# Sheet1_Drone.net
KiCad netlist of a schematic drawn in Altium Designer
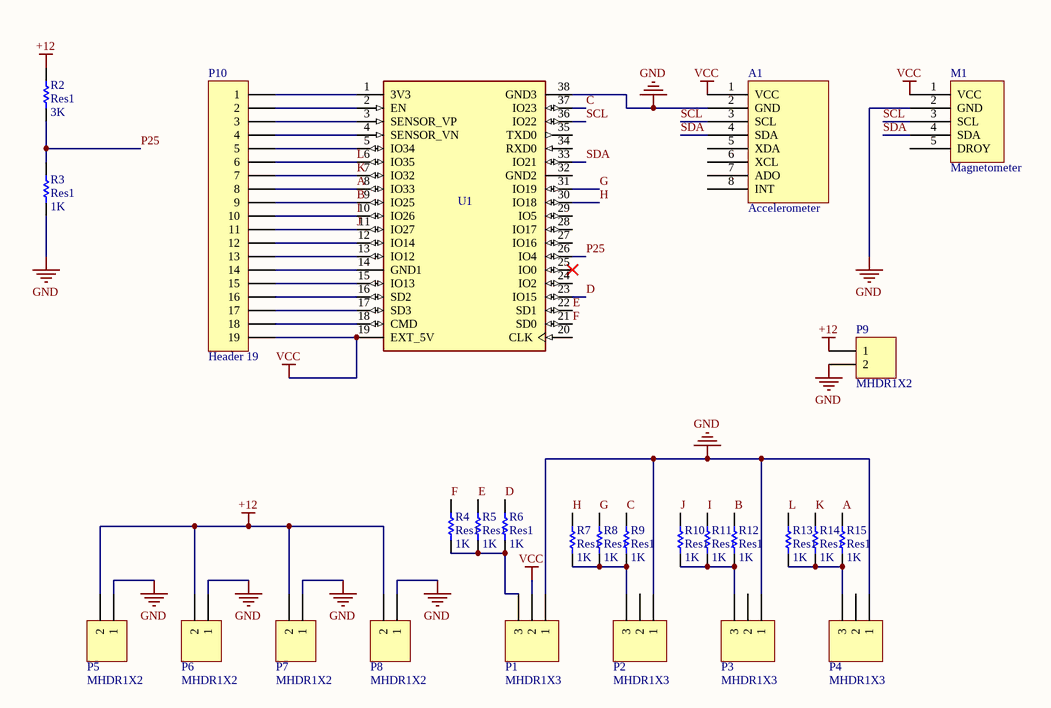
[diagram p0: Sheet1_Drone.SchDoc]

(export (version "E")
  (design (tool "Eeschema 10.0.6"))
  (components
    (comp (ref "A1")
      (value "Accelerometer")
      (footprint "Accelerometer")
      (libsource (lib "Schlib1_Drone") (part "HW123_Accelerator"))
    )
    (comp (ref "M1")
      (value "Magnetometer")
      (footprint "Magnetometer")
      (libsource (lib "Schlib1_Drone") (part "Magnetometer"))
    )
    (comp (ref "P1")
      (value "MHDR1X3")
      (footprint "SAMTEC_BBS-102-X-X")
      (description "Header, 3-Pin")
      (fields (field (name "PUBLISHER") "Altium Limited"))
      (libsource (lib "Miscellaneous Connectors") (part "MHDR1X3"))
    )
    (comp (ref "P2")
      (value "MHDR1X3")
      (footprint "SAMTEC_BBS-102-X-X")
      (description "Header, 3-Pin")
      (fields (field (name "PUBLISHER") "Altium Limited"))
      (libsource (lib "Miscellaneous Connectors") (part "MHDR1X3"))
    )
    (comp (ref "P3")
      (value "MHDR1X3")
      (footprint "SAMTEC_BBS-102-X-X")
      (description "Header, 3-Pin")
      (fields (field (name "PUBLISHER") "Altium Limited"))
      (libsource (lib "Miscellaneous Connectors") (part "MHDR1X3"))
    )
    (comp (ref "P4")
      (value "MHDR1X3")
      (footprint "SAMTEC_BBS-102-X-X")
      (description "Header, 3-Pin")
      (fields (field (name "PUBLISHER") "Altium Limited"))
      (libsource (lib "Miscellaneous Connectors") (part "MHDR1X3"))
    )
    (comp (ref "P5")
      (value "MHDR1X2")
      (footprint "XT30UPB-M")
      (description "Header, 2-Pin")
      (fields (field (name "PUBLISHER") "Altium Limited"))
      (libsource (lib "Miscellaneous Connectors") (part "MHDR1X2"))
    )
    (comp (ref "P6")
      (value "MHDR1X2")
      (footprint "XT30UPB-M")
      (description "Header, 2-Pin")
      (fields (field (name "PUBLISHER") "Altium Limited"))
      (libsource (lib "Miscellaneous Connectors") (part "MHDR1X2"))
    )
    (comp (ref "P7")
      (value "MHDR1X2")
      (footprint "XT30UPB-M")
      (description "Header, 2-Pin")
      (fields (field (name "PUBLISHER") "Altium Limited"))
      (libsource (lib "Miscellaneous Connectors") (part "MHDR1X2"))
    )
    (comp (ref "P8")
      (value "MHDR1X2")
      (footprint "XT30UPB-M")
      (description "Header, 2-Pin")
      (fields (field (name "PUBLISHER") "Altium Limited"))
      (libsource (lib "Miscellaneous Connectors") (part "MHDR1X2"))
    )
    (comp (ref "P9")
      (value "MHDR1X2")
      (footprint "AMASS_XT60-M")
      (description "Header, 2-Pin")
      (fields (field (name "PUBLISHER") "Altium Limited"))
      (libsource (lib "") (part "MHDR1X2_1"))
    )
    (comp (ref "P10")
      (value "Header 19")
      (footprint "HDR1X19")
      (description "Header, 19-Pin")
      (fields (field (name "PUBLISHER") "Altium Limited"))
      (libsource (lib "Miscellaneous Connectors") (part "Header 19"))
    )
    (comp (ref "R2")
      (value "Res1")
      (footprint "res")
      (description "Resistor")
      (fields (field (name "ALTIUM_VALUE") "3K") (field (name "PUBLISHER") "Altium Limited"))
      (libsource (lib "Miscellaneous Devices") (part "Res1"))
    )
    (comp (ref "R3")
      (value "Res1")
      (footprint "res")
      (description "Resistor")
      (fields (field (name "ALTIUM_VALUE") "1K") (field (name "PUBLISHER") "Altium Limited"))
      (libsource (lib "Miscellaneous Devices") (part "Res1"))
    )
    (comp (ref "R4")
      (value "Res1")
      (footprint "res")
      (description "Resistor")
      (fields (field (name "ALTIUM_VALUE") "1K") (field (name "PUBLISHER") "Altium Limited"))
      (libsource (lib "Miscellaneous Devices") (part "Res1"))
    )
    (comp (ref "R5")
      (value "Res1")
      (footprint "res")
      (description "Resistor")
      (fields (field (name "ALTIUM_VALUE") "1K") (field (name "PUBLISHER") "Altium Limited"))
      (libsource (lib "Miscellaneous Devices") (part "Res1"))
    )
    (comp (ref "R6")
      (value "Res1")
      (footprint "res")
      (description "Resistor")
      (fields (field (name "ALTIUM_VALUE") "1K") (field (name "PUBLISHER") "Altium Limited"))
      (libsource (lib "Miscellaneous Devices") (part "Res1"))
    )
    (comp (ref "R7")
      (value "Res1")
      (footprint "res")
      (description "Resistor")
      (fields (field (name "ALTIUM_VALUE") "1K") (field (name "PUBLISHER") "Altium Limited"))
      (libsource (lib "Miscellaneous Devices") (part "Res1"))
    )
    (comp (ref "R8")
      (value "Res1")
      (footprint "res")
      (description "Resistor")
      (fields (field (name "ALTIUM_VALUE") "1K") (field (name "PUBLISHER") "Altium Limited"))
      (libsource (lib "Miscellaneous Devices") (part "Res1"))
    )
    (comp (ref "R9")
      (value "Res1")
      (footprint "res")
      (description "Resistor")
      (fields (field (name "ALTIUM_VALUE") "1K") (field (name "PUBLISHER") "Altium Limited"))
      (libsource (lib "Miscellaneous Devices") (part "Res1"))
    )
    (comp (ref "R10")
      (value "Res1")
      (footprint "res")
      (description "Resistor")
      (fields (field (name "ALTIUM_VALUE") "1K") (field (name "PUBLISHER") "Altium Limited"))
      (libsource (lib "Miscellaneous Devices") (part "Res1"))
    )
    (comp (ref "R11")
      (value "Res1")
      (footprint "res")
      (description "Resistor")
      (fields (field (name "ALTIUM_VALUE") "1K") (field (name "PUBLISHER") "Altium Limited"))
      (libsource (lib "Miscellaneous Devices") (part "Res1"))
    )
    (comp (ref "R12")
      (value "Res1")
      (footprint "res")
      (description "Resistor")
      (fields (field (name "ALTIUM_VALUE") "1K") (field (name "PUBLISHER") "Altium Limited"))
      (libsource (lib "Miscellaneous Devices") (part "Res1"))
    )
    (comp (ref "R13")
      (value "Res1")
      (footprint "res")
      (description "Resistor")
      (fields (field (name "ALTIUM_VALUE") "1K") (field (name "PUBLISHER") "Altium Limited"))
      (libsource (lib "Miscellaneous Devices") (part "Res1"))
    )
    (comp (ref "R14")
      (value "Res1")
      (footprint "res")
      (description "Resistor")
      (fields (field (name "ALTIUM_VALUE") "1K") (field (name "PUBLISHER") "Altium Limited"))
      (libsource (lib "Miscellaneous Devices") (part "Res1"))
    )
    (comp (ref "R15")
      (value "Res1")
      (footprint "res")
      (description "Resistor")
      (fields (field (name "ALTIUM_VALUE") "1K") (field (name "PUBLISHER") "Altium Limited"))
      (libsource (lib "Miscellaneous Devices") (part "Res1"))
    )
    (comp (ref "U1")
      (value "~")
      (footprint "MODULE_ESP32-DEVKITC")
      (fields (field (name "MP") "ESP32-DEVKITC-32D-F") (field (name "MF") "Espressif Systems"))
      (libsource (lib "*") (part "ESP32-DEVKITC"))
    )
  )
  (nets
    (net (code "1") (name "+12") (class "Default")
      (node (ref "P5") (pin "2") (pinfunction "2_2") (pintype "passive"))
      (node (ref "P6") (pin "2") (pinfunction "2_2") (pintype "passive"))
      (node (ref "P7") (pin "2") (pinfunction "2_2") (pintype "passive"))
      (node (ref "P8") (pin "2") (pinfunction "2_2") (pintype "passive"))
      (node (ref "P9") (pin "1") (pinfunction "1_1") (pintype "passive"))
      (node (ref "R2") (pin "1") (pinfunction "1_1") (pintype "passive"))
    )
    (net (code "2") (name "/A") (class "Default")
      (node (ref "P10") (pin "8") (pinfunction "8_8") (pintype "passive"))
      (node (ref "R15") (pin "1") (pinfunction "1_1") (pintype "passive"))
      (node (ref "U1") (pin "8") (pinfunction "IO33_8") (pintype "bidirectional"))
    )
    (net (code "3") (name "/B") (class "Default")
      (node (ref "P10") (pin "9") (pinfunction "9_9") (pintype "passive"))
      (node (ref "R12") (pin "1") (pinfunction "1_1") (pintype "passive"))
      (node (ref "U1") (pin "9") (pinfunction "IO25_9") (pintype "bidirectional"))
    )
    (net (code "4") (name "/C") (class "Default")
      (node (ref "R9") (pin "1") (pinfunction "1_1") (pintype "passive"))
      (node (ref "U1") (pin "37") (pinfunction "IO23_37") (pintype "bidirectional"))
    )
    (net (code "5") (name "/D") (class "Default")
      (node (ref "R6") (pin "1") (pinfunction "1_1") (pintype "passive"))
      (node (ref "U1") (pin "23") (pinfunction "IO15_23") (pintype "bidirectional"))
    )
    (net (code "6") (name "/E") (class "Default")
      (node (ref "R5") (pin "2") (pinfunction "2_2") (pintype "passive"))
      (node (ref "U1") (pin "22") (pinfunction "SD1_22") (pintype "bidirectional"))
    )
    (net (code "7") (name "/F") (class "Default")
      (node (ref "R4") (pin "1") (pinfunction "1_1") (pintype "passive"))
      (node (ref "U1") (pin "21") (pinfunction "SD0_21") (pintype "bidirectional"))
    )
    (net (code "8") (name "/G") (class "Default")
      (node (ref "R8") (pin "2") (pinfunction "2_2") (pintype "passive"))
      (node (ref "U1") (pin "31") (pinfunction "IO19_31") (pintype "bidirectional"))
    )
    (net (code "9") (name "/H") (class "Default")
      (node (ref "R7") (pin "1") (pinfunction "1_1") (pintype "passive"))
      (node (ref "U1") (pin "30") (pinfunction "IO18_30") (pintype "bidirectional"))
    )
    (net (code "10") (name "/I") (class "Default")
      (node (ref "P10") (pin "10") (pinfunction "10_10") (pintype "passive"))
      (node (ref "R11") (pin "2") (pinfunction "2_2") (pintype "passive"))
      (node (ref "U1") (pin "10") (pinfunction "IO26_10") (pintype "bidirectional"))
    )
    (net (code "11") (name "/J") (class "Default")
      (node (ref "P10") (pin "11") (pinfunction "11_11") (pintype "passive"))
      (node (ref "R10") (pin "1") (pinfunction "1_1") (pintype "passive"))
      (node (ref "U1") (pin "11") (pinfunction "IO27_11") (pintype "bidirectional"))
    )
    (net (code "12") (name "/K") (class "Default")
      (node (ref "P10") (pin "7") (pinfunction "7_7") (pintype "passive"))
      (node (ref "R14") (pin "2") (pinfunction "2_2") (pintype "passive"))
      (node (ref "U1") (pin "7") (pinfunction "IO32_7") (pintype "bidirectional"))
    )
    (net (code "13") (name "/L") (class "Default")
      (node (ref "P10") (pin "6") (pinfunction "6_6") (pintype "passive"))
      (node (ref "R13") (pin "1") (pinfunction "1_1") (pintype "passive"))
      (node (ref "U1") (pin "6") (pinfunction "IO35_6") (pintype "bidirectional"))
    )
    (net (code "14") (name "/P25") (class "Default")
      (node (ref "R2") (pin "2") (pinfunction "2_2") (pintype "passive"))
      (node (ref "R3") (pin "1") (pinfunction "1_1") (pintype "passive"))
      (node (ref "U1") (pin "26") (pinfunction "IO4_26") (pintype "bidirectional"))
    )
    (net (code "15") (name "/SCL") (class "Default")
      (node (ref "A1") (pin "3") (pinfunction "SCL_3") (pintype "passive"))
      (node (ref "M1") (pin "3") (pinfunction "SCL_3") (pintype "passive"))
      (node (ref "U1") (pin "36") (pinfunction "IO22_36") (pintype "bidirectional"))
    )
    (net (code "16") (name "/SDA") (class "Default")
      (node (ref "A1") (pin "4") (pinfunction "SDA_4") (pintype "passive"))
      (node (ref "M1") (pin "4") (pinfunction "SDA_4") (pintype "passive"))
      (node (ref "U1") (pin "33") (pinfunction "IO21_33") (pintype "bidirectional"))
    )
    (net (code "17") (name "GND") (class "Default")
      (node (ref "A1") (pin "2") (pinfunction "GND_2") (pintype "passive"))
      (node (ref "M1") (pin "2") (pinfunction "GND_2") (pintype "passive"))
      (node (ref "P1") (pin "1") (pinfunction "1_1") (pintype "passive"))
      (node (ref "P2") (pin "1") (pinfunction "1_1") (pintype "passive"))
      (node (ref "P3") (pin "1") (pinfunction "1_1") (pintype "passive"))
      (node (ref "P4") (pin "1") (pinfunction "1_1") (pintype "passive"))
      (node (ref "P5") (pin "1") (pinfunction "1_1") (pintype "passive"))
      (node (ref "P6") (pin "1") (pinfunction "1_1") (pintype "passive"))
      (node (ref "P7") (pin "1") (pinfunction "1_1") (pintype "passive"))
      (node (ref "P8") (pin "1") (pinfunction "1_1") (pintype "passive"))
      (node (ref "P9") (pin "2") (pinfunction "2_2") (pintype "passive"))
      (node (ref "R3") (pin "2") (pinfunction "2_2") (pintype "passive"))
      (node (ref "U1") (pin "38") (pinfunction "GND3_38") (pintype "power_in"))
    )
    (net (code "18") (name "Net-(P1-Pad3)") (class "Default")
      (node (ref "P1") (pin "3") (pinfunction "3_3") (pintype "passive"))
      (node (ref "R4") (pin "2") (pinfunction "2_2") (pintype "passive"))
      (node (ref "R5") (pin "1") (pinfunction "1_1") (pintype "passive"))
      (node (ref "R6") (pin "2") (pinfunction "2_2") (pintype "passive"))
    )
    (net (code "19") (name "Net-(P2-Pad3)") (class "Default")
      (node (ref "P2") (pin "3") (pinfunction "3_3") (pintype "passive"))
      (node (ref "R7") (pin "2") (pinfunction "2_2") (pintype "passive"))
      (node (ref "R8") (pin "1") (pinfunction "1_1") (pintype "passive"))
      (node (ref "R9") (pin "2") (pinfunction "2_2") (pintype "passive"))
    )
    (net (code "20") (name "Net-(P3-Pad3)") (class "Default")
      (node (ref "P3") (pin "3") (pinfunction "3_3") (pintype "passive"))
      (node (ref "R10") (pin "2") (pinfunction "2_2") (pintype "passive"))
      (node (ref "R11") (pin "1") (pinfunction "1_1") (pintype "passive"))
      (node (ref "R12") (pin "2") (pinfunction "2_2") (pintype "passive"))
    )
    (net (code "21") (name "Net-(P4-Pad3)") (class "Default")
      (node (ref "P4") (pin "3") (pinfunction "3_3") (pintype "passive"))
      (node (ref "R13") (pin "2") (pinfunction "2_2") (pintype "passive"))
      (node (ref "R14") (pin "1") (pinfunction "1_1") (pintype "passive"))
      (node (ref "R15") (pin "2") (pinfunction "2_2") (pintype "passive"))
    )
    (net (code "22") (name "Net-(U1-3V3)") (class "Default")
      (node (ref "P10") (pin "1") (pinfunction "1_1") (pintype "passive"))
      (node (ref "U1") (pin "1") (pinfunction "3V3_1") (pintype "power_in"))
    )
    (net (code "23") (name "Net-(U1-CMD)") (class "Default")
      (node (ref "P10") (pin "18") (pinfunction "18_18") (pintype "passive"))
      (node (ref "U1") (pin "18") (pinfunction "CMD_18") (pintype "bidirectional"))
    )
    (net (code "24") (name "Net-(U1-EN)") (class "Default")
      (node (ref "P10") (pin "2") (pinfunction "2_2") (pintype "passive"))
      (node (ref "U1") (pin "2") (pinfunction "EN_2") (pintype "input"))
    )
    (net (code "25") (name "Net-(U1-GND1)") (class "Default")
      (node (ref "P10") (pin "14") (pinfunction "14_14") (pintype "passive"))
      (node (ref "U1") (pin "14") (pinfunction "GND1_14") (pintype "power_in"))
    )
    (net (code "26") (name "Net-(U1-IO12)") (class "Default")
      (node (ref "P10") (pin "13") (pinfunction "13_13") (pintype "passive"))
      (node (ref "U1") (pin "13") (pinfunction "IO12_13") (pintype "bidirectional"))
    )
    (net (code "27") (name "Net-(U1-IO13)") (class "Default")
      (node (ref "P10") (pin "15") (pinfunction "15_15") (pintype "passive"))
      (node (ref "U1") (pin "15") (pinfunction "IO13_15") (pintype "bidirectional"))
    )
    (net (code "28") (name "Net-(U1-IO14)") (class "Default")
      (node (ref "P10") (pin "12") (pinfunction "12_12") (pintype "passive"))
      (node (ref "U1") (pin "12") (pinfunction "IO14_12") (pintype "bidirectional"))
    )
    (net (code "29") (name "Net-(U1-IO34)") (class "Default")
      (node (ref "P10") (pin "5") (pinfunction "5_5") (pintype "passive"))
      (node (ref "U1") (pin "5") (pinfunction "IO34_5") (pintype "bidirectional"))
    )
    (net (code "30") (name "Net-(U1-SD2)") (class "Default")
      (node (ref "P10") (pin "16") (pinfunction "16_16") (pintype "passive"))
      (node (ref "U1") (pin "16") (pinfunction "SD2_16") (pintype "bidirectional"))
    )
    (net (code "31") (name "Net-(U1-SD3)") (class "Default")
      (node (ref "P10") (pin "17") (pinfunction "17_17") (pintype "passive"))
      (node (ref "U1") (pin "17") (pinfunction "SD3_17") (pintype "bidirectional"))
    )
    (net (code "32") (name "Net-(U1-SENSOR_VN)") (class "Default")
      (node (ref "P10") (pin "4") (pinfunction "4_4") (pintype "passive"))
      (node (ref "U1") (pin "4") (pinfunction "SENSOR_VN_4") (pintype "input"))
    )
    (net (code "33") (name "Net-(U1-SENSOR_VP)") (class "Default")
      (node (ref "P10") (pin "3") (pinfunction "3_3") (pintype "passive"))
      (node (ref "U1") (pin "3") (pinfunction "SENSOR_VP_3") (pintype "input"))
    )
    (net (code "34") (name "VCC") (class "Default")
      (node (ref "A1") (pin "1") (pinfunction "VCC_1") (pintype "passive"))
      (node (ref "M1") (pin "1") (pinfunction "VCC_1") (pintype "passive"))
      (node (ref "P1") (pin "2") (pinfunction "2_2") (pintype "passive"))
      (node (ref "P10") (pin "19") (pinfunction "19_19") (pintype "passive"))
      (node (ref "U1") (pin "19") (pinfunction "EXT_5V_19") (pintype "power_in"))
    )
    (net (code "35") (name "unconnected-(A1-ADO-Pad7)") (class "Default")
      (node (ref "A1") (pin "7") (pinfunction "ADO_7") (pintype "passive"))
    )
    (net (code "36") (name "unconnected-(A1-INT-Pad8)") (class "Default")
      (node (ref "A1") (pin "8") (pinfunction "INT_8") (pintype "passive"))
    )
    (net (code "37") (name "unconnected-(A1-XCL-Pad6)") (class "Default")
      (node (ref "A1") (pin "6") (pinfunction "XCL_6") (pintype "passive"))
    )
    (net (code "38") (name "unconnected-(A1-XDA-Pad5)") (class "Default")
      (node (ref "A1") (pin "5") (pinfunction "XDA_5") (pintype "passive"))
    )
    (net (code "39") (name "unconnected-(M1-DROY-Pad5)") (class "Default")
      (node (ref "M1") (pin "5") (pinfunction "DROY_5") (pintype "passive"))
    )
    (net (code "40") (name "unconnected-(P2-Pad2)") (class "Default")
      (node (ref "P2") (pin "2") (pinfunction "2_2") (pintype "passive"))
    )
    (net (code "41") (name "unconnected-(P3-Pad2)") (class "Default")
      (node (ref "P3") (pin "2") (pinfunction "2_2") (pintype "passive"))
    )
    (net (code "42") (name "unconnected-(P4-Pad2)") (class "Default")
      (node (ref "P4") (pin "2") (pinfunction "2_2") (pintype "passive"))
    )
    (net (code "43") (name "unconnected-(U1-CLK-Pad20)") (class "Default")
      (node (ref "U1") (pin "20") (pinfunction "CLK_20") (pintype "input"))
    )
    (net (code "44") (name "unconnected-(U1-GND2-Pad32)") (class "Default")
      (node (ref "U1") (pin "32") (pinfunction "GND2_32") (pintype "power_in"))
    )
    (net (code "45") (name "unconnected-(U1-IO0-Pad25)") (class "Default")
      (node (ref "U1") (pin "25") (pinfunction "IO0_25") (pintype "bidirectional+no_connect"))
    )
    (net (code "46") (name "unconnected-(U1-IO2-Pad24)") (class "Default")
      (node (ref "U1") (pin "24") (pinfunction "IO2_24") (pintype "bidirectional"))
    )
    (net (code "47") (name "unconnected-(U1-IO5-Pad29)") (class "Default")
      (node (ref "U1") (pin "29") (pinfunction "IO5_29") (pintype "bidirectional"))
    )
    (net (code "48") (name "unconnected-(U1-IO16-Pad27)") (class "Default")
      (node (ref "U1") (pin "27") (pinfunction "IO16_27") (pintype "bidirectional"))
    )
    (net (code "49") (name "unconnected-(U1-IO17-Pad28)") (class "Default")
      (node (ref "U1") (pin "28") (pinfunction "IO17_28") (pintype "bidirectional"))
    )
    (net (code "50") (name "unconnected-(U1-RXD0-Pad34)") (class "Default")
      (node (ref "U1") (pin "34") (pinfunction "RXD0_34") (pintype "input"))
    )
    (net (code "51") (name "unconnected-(U1-TXD0-Pad35)") (class "Default")
      (node (ref "U1") (pin "35") (pinfunction "TXD0_35") (pintype "output"))
    )
  )
)
